# PWR_P1V8A.net
KiCad netlist of a schematic drawn in Altium Designer
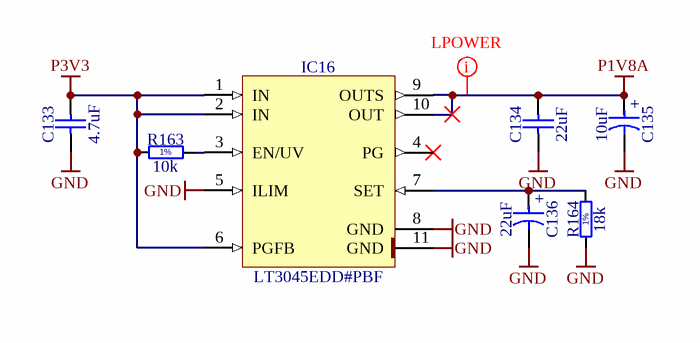
[diagram p0: PWR_P1V8A.SchDoc]

(export (version "E")
  (design (tool "Eeschema 10.0.6"))
  (components
    (comp (ref "C133")
      (value "4.7uF")
      (footprint "CAPC1709X95N")
      (description "Non-polarised capacitor")
      (fields
        (field (name "PART NUMBER") "CC0603_4.7UF_16V_10%_X5R")
        (field (name "VOLTAGE") "16V")
        (field (name "AUTHOR") "CERN DEM JLC")
      )
      (libsource (lib "Capacitors") (part "Capacitor - non polarized"))
    )
    (comp (ref "C134")
      (value "22uF")
      (footprint "CAPC2012X135N")
      (description "Non-polarised capacitor")
      (fields
        (field (name "PART NUMBER") "CC0805_22UF_16V_10%_X5R")
        (field (name "VOLTAGE") "16V")
        (field (name "AUTHOR") "CERN DEM JLC")
      )
      (libsource (lib "Capacitors") (part "Capacitor - non polarized"))
    )
    (comp (ref "C135")
      (value "10uF")
      (footprint "CAPMP3216X180N")
      (description "Polarised capacitor")
      (fields
        (field (name "PART NUMBER") "CTE3216-18_10UF_16V_20%_AVX_TCJ")
        (field (name "VOLTAGE") "16V")
        (field (name "AUTHOR") "CERN DEM JLC")
      )
      (libsource (lib "Capacitors") (part "Capacitor - polarized"))
    )
    (comp (ref "C136")
      (value "22uF")
      (footprint "CAPMP3216X180N")
      (description "Polarised capacitor")
      (fields
        (field (name "PART NUMBER") "CTE3216-18_22UF_10V_10%")
        (field (name "VOLTAGE") "10V")
        (field (name "AUTHOR") "CERN DEM JLC")
      )
      (libsource (lib "Capacitors") (part "Capacitor - polarized"))
    )
    (comp (ref "IC16")
      (value "LT3045EDD#PBF")
      (footprint "SON50P300X300X80-11N-R175X248")
      (description "20V, 500mA, Ultralow Noise, Ultrahigh PSRR Linear Regulator")
      (fields (field (name "MANUFACTURER") "LINEAR TECHNOLOGY") (field (name "AUTHOR") "CERN DEM JLC"))
      (libsource (lib "ICs And Semiconductors") (part "LT3045EDD"))
    )
    (comp (ref "R163")
      (value "10k")
      (footprint "RESC1005X40N")
      (description "Resistor - 1%")
      (fields
        (field (name "PART NUMBER") "R0402_10K_1%_0.0625W_100PPM")
        (field (name "POWER") "0.0625W")
        (field (name "AUTHOR") "CERN DEM JLC")
      )
      (libsource (lib "Resistors") (part "Resistor - 1%"))
    )
    (comp (ref "R164")
      (value "18k")
      (footprint "RESC1608X55N")
      (description "Resistor - 1%")
      (fields
        (field (name "PART NUMBER") "R0603_18K_1%_0.1W_100PPM")
        (field (name "POWER") "0.1W")
        (field (name "AUTHOR") "CERN DEM JLC")
      )
      (libsource (lib "Resistors") (part "Resistor - 1%"))
    )
  )
  (nets
    (net (code "1") (name "GND") (class "Default")
      (node (ref "C133") (pin "1") (pinfunction "1_1") (pintype "passive"))
      (node (ref "C134") (pin "1") (pinfunction "1_1") (pintype "passive"))
      (node (ref "C135") (pin "2") (pinfunction "2_2") (pintype "passive"))
      (node (ref "C136") (pin "2") (pinfunction "2_2") (pintype "passive"))
      (node (ref "IC16") (pin "11") (pinfunction "GND_11") (pintype "power_in"))
      (node (ref "IC16") (pin "5") (pinfunction "ILIM_5") (pintype "input"))
      (node (ref "IC16") (pin "8") (pinfunction "GND_8") (pintype "power_in"))
      (node (ref "R164") (pin "1") (pinfunction "1_1") (pintype "passive"))
    )
    (net (code "2") (name "Net-(IC16-EN{slash}UV)") (class "Default")
      (node (ref "IC16") (pin "3") (pinfunction "EN/UV_3") (pintype "input"))
      (node (ref "R163") (pin "2") (pinfunction "2_2") (pintype "passive"))
    )
    (net (code "3") (name "Net-(IC16-SET)") (class "Default")
      (node (ref "C136") (pin "1") (pinfunction "1_1") (pintype "passive"))
      (node (ref "IC16") (pin "7") (pinfunction "SET_7") (pintype "input"))
      (node (ref "R164") (pin "2") (pinfunction "2_2") (pintype "passive"))
    )
    (net (code "4") (name "P1V8A") (class "Default")
      (node (ref "C134") (pin "2") (pinfunction "2_2") (pintype "passive"))
      (node (ref "C135") (pin "1") (pinfunction "1_1") (pintype "passive"))
      (node (ref "IC16") (pin "10") (pinfunction "OUT_10") (pintype "output"))
      (node (ref "IC16") (pin "9") (pinfunction "OUTS_9") (pintype "output"))
    )
    (net (code "5") (name "P3V3") (class "Default")
      (node (ref "C133") (pin "2") (pinfunction "2_2") (pintype "passive"))
      (node (ref "IC16") (pin "1") (pinfunction "IN_1") (pintype "input"))
      (node (ref "IC16") (pin "2") (pinfunction "IN_2") (pintype "input"))
      (node (ref "IC16") (pin "6") (pinfunction "PGFB_6") (pintype "input"))
      (node (ref "R163") (pin "1") (pinfunction "1_1") (pintype "passive"))
    )
    (net (code "6") (name "unconnected-(IC16-PG-Pad4)") (class "Default")
      (node (ref "IC16") (pin "4") (pinfunction "PG_4") (pintype "output+no_connect"))
    )
  )
)
